# acromegaly.net
KiCad netlist of a schematic drawn in EAGLE
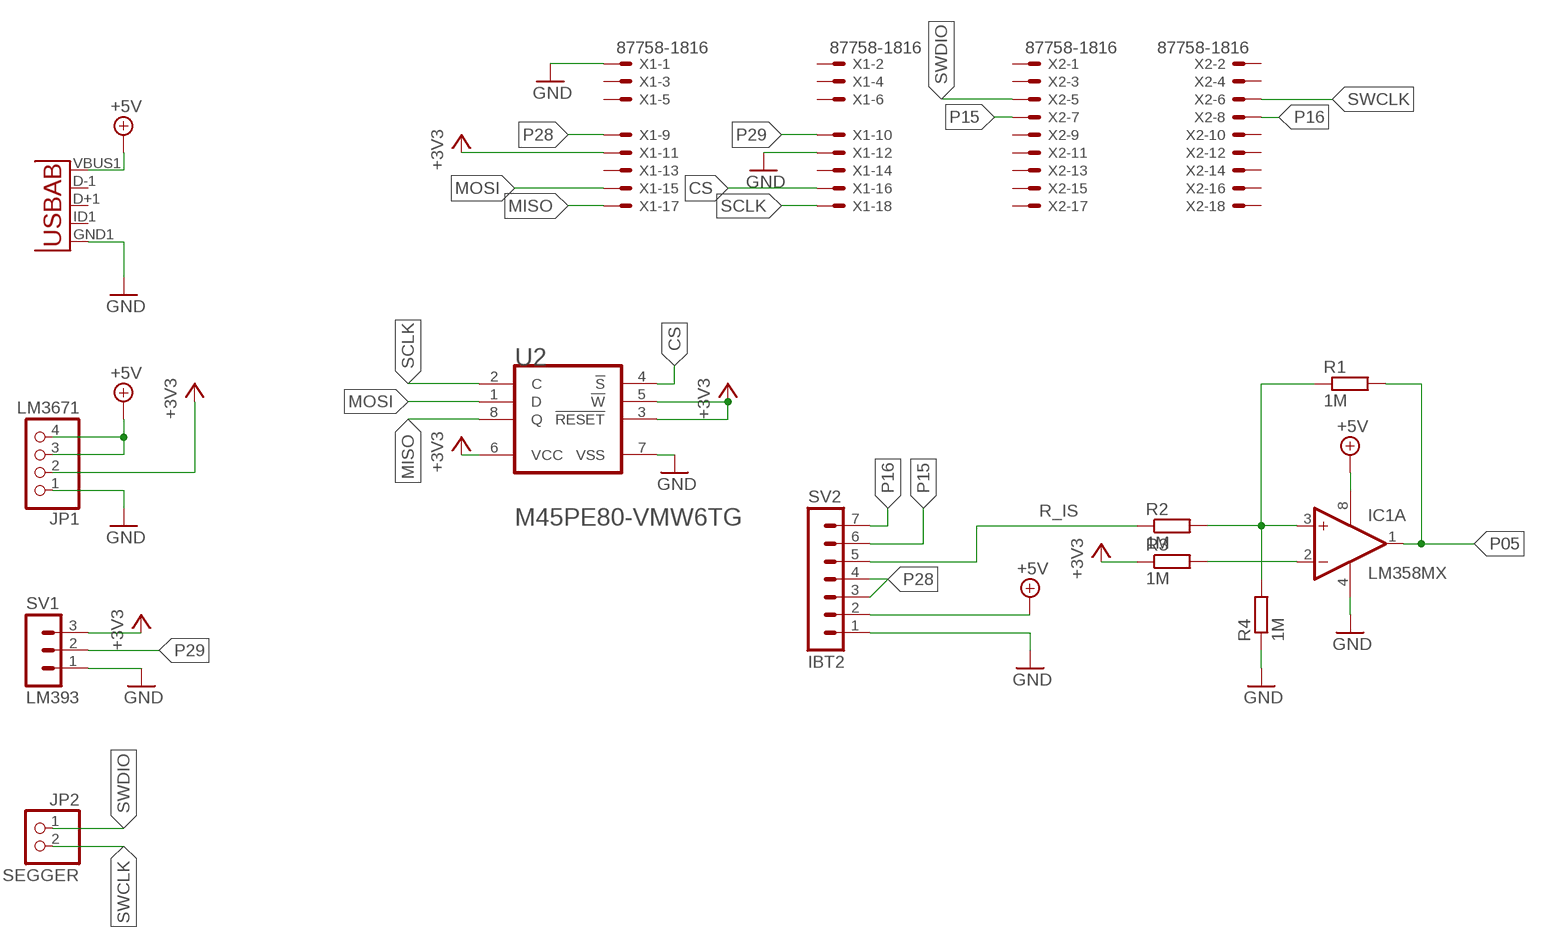
[diagram p0: schematic, sheet 1]

(export (version "E")
  (design (tool "Eeschema 10.0.6"))
  (components
    (comp (ref "IC1")
      (value "LM358MX")
      (footprint "eagle-import:SO08")
      (libsource (lib "eagle-import") (part "LM358MX"))
    )
    (comp (ref "JP1")
      (value "LM3671")
      (footprint "eagle-import:1X04")
      (libsource (lib "eagle-import") (part "PINHD-1X4"))
    )
    (comp (ref "JP2")
      (value "SEGGER")
      (footprint "eagle-import:1X02")
      (libsource (lib "eagle-import") (part "PINHD-1X2"))
    )
    (comp (ref "R1")
      (value "1M")
      (footprint "eagle-import:M1206")
      (libsource (lib "eagle-import") (part "R-EU_M1206"))
    )
    (comp (ref "R2")
      (value "1M")
      (footprint "eagle-import:M1206")
      (libsource (lib "eagle-import") (part "R-EU_M1206"))
    )
    (comp (ref "R3")
      (value "1M")
      (footprint "eagle-import:M1206")
      (libsource (lib "eagle-import") (part "R-EU_M1206"))
    )
    (comp (ref "R4")
      (value "1M")
      (footprint "eagle-import:M1206")
      (libsource (lib "eagle-import") (part "R-EU_M1206"))
    )
    (comp (ref "SV1")
      (value "LM393")
      (footprint "eagle-import:MA03-1")
      (libsource (lib "eagle-import") (part "MA03-1"))
    )
    (comp (ref "SV2")
      (value "IBT2")
      (footprint "eagle-import:MA07-1")
      (libsource (lib "eagle-import") (part "MA07-1"))
    )
    (comp (ref "U1")
      (value "USB\"\"")
      (footprint "eagle-import:USB-MICRO-SMD")
      (libsource (lib "eagle-import") (part "USB{dblquote}{dblquote}"))
    )
    (comp (ref "U2")
      (value "MICRON_M45PE80-VMW6TGMICRON_M45PE80-VMW6TG_0_0")
      (footprint "eagle-import:MICRON_M45PE80-VMW6TG_0")
      (fields
        (field (name "MF") "Micron")
        (field (name "MPN") "M45PE80-VMW6TG")
        (field (name "VOLTAGE") "2.7V-3.6VÂ ")
      )
      (libsource (lib "eagle-import") (part "MICRON_M45PE80-VMW6TGMICRON_M45PE80-VMW6TG_0_0"))
    )
    (comp (ref "X1")
      (value "87758-1816")
      (footprint "eagle-import:87758-1816")
      (fields (field (name "MF") "MOLEX"))
      (libsource (lib "eagle-import") (part "87758-1816"))
    )
    (comp (ref "X2")
      (value "87758-1816")
      (footprint "eagle-import:87758-1816")
      (fields (field (name "MF") "MOLEX"))
      (libsource (lib "eagle-import") (part "87758-1816"))
    )
  )
  (nets
    (net (code "1") (name "+3V3") (class "Default")
      (node (ref "JP1") (pin "2") (pinfunction "2_2") (pintype "passive"))
      (node (ref "R3") (pin "1") (pinfunction "1_1") (pintype "passive"))
      (node (ref "SV1") (pin "3") (pinfunction "3_3") (pintype "passive"))
      (node (ref "U2") (pin "3") (pinfunction "~{RESET}_3") (pintype "input"))
      (node (ref "U2") (pin "5") (pinfunction "~{W}_5") (pintype "input"))
      (node (ref "U2") (pin "6") (pinfunction "VCC_6") (pintype "power_in"))
      (node (ref "X1") (pin "11") (pinfunction "S_11") (pintype "passive"))
    )
    (net (code "2") (name "+5V") (class "Default")
      (node (ref "IC1") (pin "8") (pinfunction "V+_8") (pintype "power_in"))
      (node (ref "JP1") (pin "3") (pinfunction "3_3") (pintype "passive"))
      (node (ref "JP1") (pin "4") (pinfunction "4_4") (pintype "passive"))
      (node (ref "SV2") (pin "2") (pinfunction "2_2") (pintype "passive"))
      (node (ref "U1") (pin "VBUS1") (pinfunction "VBUS_VBUS1") (pintype "bidirectional"))
    )
    (net (code "3") (name "/R_IS") (class "Default")
      (node (ref "R2") (pin "1") (pinfunction "1_1") (pintype "passive"))
      (node (ref "SV2") (pin "5") (pinfunction "5_5") (pintype "passive"))
    )
    (net (code "4") (name "CS") (class "Default")
      (node (ref "U2") (pin "4") (pinfunction "~{S}_4") (pintype "input"))
      (node (ref "X1") (pin "16") (pinfunction "S_16") (pintype "passive"))
    )
    (net (code "5") (name "GND") (class "Default")
      (node (ref "IC1") (pin "4") (pinfunction "V-_4") (pintype "power_in"))
      (node (ref "JP1") (pin "1") (pinfunction "1_1") (pintype "passive"))
      (node (ref "R4") (pin "1") (pinfunction "1_1") (pintype "passive"))
      (node (ref "SV1") (pin "1") (pinfunction "1_1") (pintype "passive"))
      (node (ref "SV2") (pin "1") (pinfunction "1_1") (pintype "passive"))
      (node (ref "U1") (pin "GND1") (pinfunction "GND_GND1") (pintype "bidirectional"))
      (node (ref "U2") (pin "7") (pinfunction "VSS_7") (pintype "power_in"))
      (node (ref "X1") (pin "1") (pinfunction "S_1") (pintype "passive"))
      (node (ref "X1") (pin "12") (pinfunction "S_12") (pintype "passive"))
    )
    (net (code "6") (name "MISO") (class "Default")
      (node (ref "U2") (pin "8") (pinfunction "Q_8") (pintype "tri_state"))
      (node (ref "X1") (pin "17") (pinfunction "S_17") (pintype "passive"))
    )
    (net (code "7") (name "MOSI") (class "Default")
      (node (ref "U2") (pin "1") (pinfunction "D_1") (pintype "input"))
      (node (ref "X1") (pin "15") (pinfunction "S_15") (pintype "passive"))
    )
    (net (code "8") (name "Net-(IC1A-+IN)") (class "Default")
      (node (ref "IC1") (pin "3") (pinfunction "+IN_3") (pintype "input"))
      (node (ref "R1") (pin "1") (pinfunction "1_1") (pintype "passive"))
      (node (ref "R2") (pin "2") (pinfunction "2_2") (pintype "passive"))
      (node (ref "R4") (pin "2") (pinfunction "2_2") (pintype "passive"))
    )
    (net (code "9") (name "Net-(IC1A--IN)") (class "Default")
      (node (ref "IC1") (pin "2") (pinfunction "-IN_2") (pintype "input"))
      (node (ref "R3") (pin "2") (pinfunction "2_2") (pintype "passive"))
    )
    (net (code "10") (name "P05") (class "Default")
      (node (ref "IC1") (pin "1") (pinfunction "OUT_1") (pintype "output"))
      (node (ref "R1") (pin "2") (pinfunction "2_2") (pintype "passive"))
    )
    (net (code "11") (name "P15") (class "Default")
      (node (ref "SV2") (pin "6") (pinfunction "6_6") (pintype "passive"))
      (node (ref "X2") (pin "7") (pinfunction "S_7") (pintype "passive"))
    )
    (net (code "12") (name "P16") (class "Default")
      (node (ref "SV2") (pin "7") (pinfunction "7_7") (pintype "passive"))
      (node (ref "X2") (pin "8") (pinfunction "S_8") (pintype "passive"))
    )
    (net (code "13") (name "P28") (class "Default")
      (node (ref "SV2") (pin "3") (pinfunction "3_3") (pintype "passive"))
      (node (ref "SV2") (pin "4") (pinfunction "4_4") (pintype "passive"))
      (node (ref "X1") (pin "9") (pinfunction "S_9") (pintype "passive"))
    )
    (net (code "14") (name "P29") (class "Default")
      (node (ref "SV1") (pin "2") (pinfunction "2_2") (pintype "passive"))
      (node (ref "X1") (pin "10") (pinfunction "S_10") (pintype "passive"))
    )
    (net (code "15") (name "SCLK") (class "Default")
      (node (ref "U2") (pin "2") (pinfunction "C_2") (pintype "input"))
      (node (ref "X1") (pin "18") (pinfunction "S_18") (pintype "passive"))
    )
    (net (code "16") (name "SWCLK") (class "Default")
      (node (ref "JP2") (pin "2") (pinfunction "2_2") (pintype "passive"))
      (node (ref "X2") (pin "6") (pinfunction "S_6") (pintype "passive"))
    )
    (net (code "17") (name "SWDIO") (class "Default")
      (node (ref "JP2") (pin "1") (pinfunction "1_1") (pintype "passive"))
      (node (ref "X2") (pin "5") (pinfunction "S_5") (pintype "passive"))
    )
    (net (code "18") (name "unconnected-(U1-D+-PadD+1)") (class "Default")
      (node (ref "U1") (pin "D+1") (pinfunction "D+_D+1") (pintype "bidirectional"))
    )
    (net (code "19") (name "unconnected-(U1-D--PadD-1)") (class "Default")
      (node (ref "U1") (pin "D-1") (pinfunction "D-_D-1") (pintype "bidirectional"))
    )
    (net (code "20") (name "unconnected-(U1-USBID-PadID1)") (class "Default")
      (node (ref "U1") (pin "ID1") (pinfunction "USBID_ID1") (pintype "bidirectional"))
    )
    (net (code "21") (name "unconnected-(X1E-S-Pad13)") (class "Default")
      (node (ref "X1") (pin "13") (pinfunction "S_13") (pintype "passive"))
    )
    (net (code "22") (name "unconnected-(X1F-S-Pad14)") (class "Default")
      (node (ref "X1") (pin "14") (pinfunction "S_14") (pintype "passive"))
    )
    (net (code "23") (name "unconnected-(X1K-S-Pad2)") (class "Default")
      (node (ref "X1") (pin "2") (pinfunction "S_2") (pintype "passive"))
    )
    (net (code "24") (name "unconnected-(X1L-S-Pad3)") (class "Default")
      (node (ref "X1") (pin "3") (pinfunction "S_3") (pintype "passive"))
    )
    (net (code "25") (name "unconnected-(X1M-S-Pad4)") (class "Default")
      (node (ref "X1") (pin "4") (pinfunction "S_4") (pintype "passive"))
    )
    (net (code "26") (name "unconnected-(X1N-S-Pad5)") (class "Default")
      (node (ref "X1") (pin "5") (pinfunction "S_5") (pintype "passive"))
    )
    (net (code "27") (name "unconnected-(X1O-S-Pad6)") (class "Default")
      (node (ref "X1") (pin "6") (pinfunction "S_6") (pintype "passive"))
    )
    (net (code "28") (name "unconnected-(X2A-S-Pad1)") (class "Default")
      (node (ref "X2") (pin "1") (pinfunction "S_1") (pintype "passive"))
    )
    (net (code "29") (name "unconnected-(X2B-S-Pad10)") (class "Default")
      (node (ref "X2") (pin "10") (pinfunction "S_10") (pintype "passive"))
    )
    (net (code "30") (name "unconnected-(X2C-S-Pad11)") (class "Default")
      (node (ref "X2") (pin "11") (pinfunction "S_11") (pintype "passive"))
    )
    (net (code "31") (name "unconnected-(X2D-S-Pad12)") (class "Default")
      (node (ref "X2") (pin "12") (pinfunction "S_12") (pintype "passive"))
    )
    (net (code "32") (name "unconnected-(X2E-S-Pad13)") (class "Default")
      (node (ref "X2") (pin "13") (pinfunction "S_13") (pintype "passive"))
    )
    (net (code "33") (name "unconnected-(X2F-S-Pad14)") (class "Default")
      (node (ref "X2") (pin "14") (pinfunction "S_14") (pintype "passive"))
    )
    (net (code "34") (name "unconnected-(X2G-S-Pad15)") (class "Default")
      (node (ref "X2") (pin "15") (pinfunction "S_15") (pintype "passive"))
    )
    (net (code "35") (name "unconnected-(X2H-S-Pad16)") (class "Default")
      (node (ref "X2") (pin "16") (pinfunction "S_16") (pintype "passive"))
    )
    (net (code "36") (name "unconnected-(X2I-S-Pad17)") (class "Default")
      (node (ref "X2") (pin "17") (pinfunction "S_17") (pintype "passive"))
    )
    (net (code "37") (name "unconnected-(X2J-S-Pad18)") (class "Default")
      (node (ref "X2") (pin "18") (pinfunction "S_18") (pintype "passive"))
    )
    (net (code "38") (name "unconnected-(X2K-S-Pad2)") (class "Default")
      (node (ref "X2") (pin "2") (pinfunction "S_2") (pintype "passive"))
    )
    (net (code "39") (name "unconnected-(X2L-S-Pad3)") (class "Default")
      (node (ref "X2") (pin "3") (pinfunction "S_3") (pintype "passive"))
    )
    (net (code "40") (name "unconnected-(X2M-S-Pad4)") (class "Default")
      (node (ref "X2") (pin "4") (pinfunction "S_4") (pintype "passive"))
    )
    (net (code "41") (name "unconnected-(X2R-S-Pad9)") (class "Default")
      (node (ref "X2") (pin "9") (pinfunction "S_9") (pintype "passive"))
    )
  )
)
